# PIC32.net
KiCad netlist of a schematic drawn in EAGLE
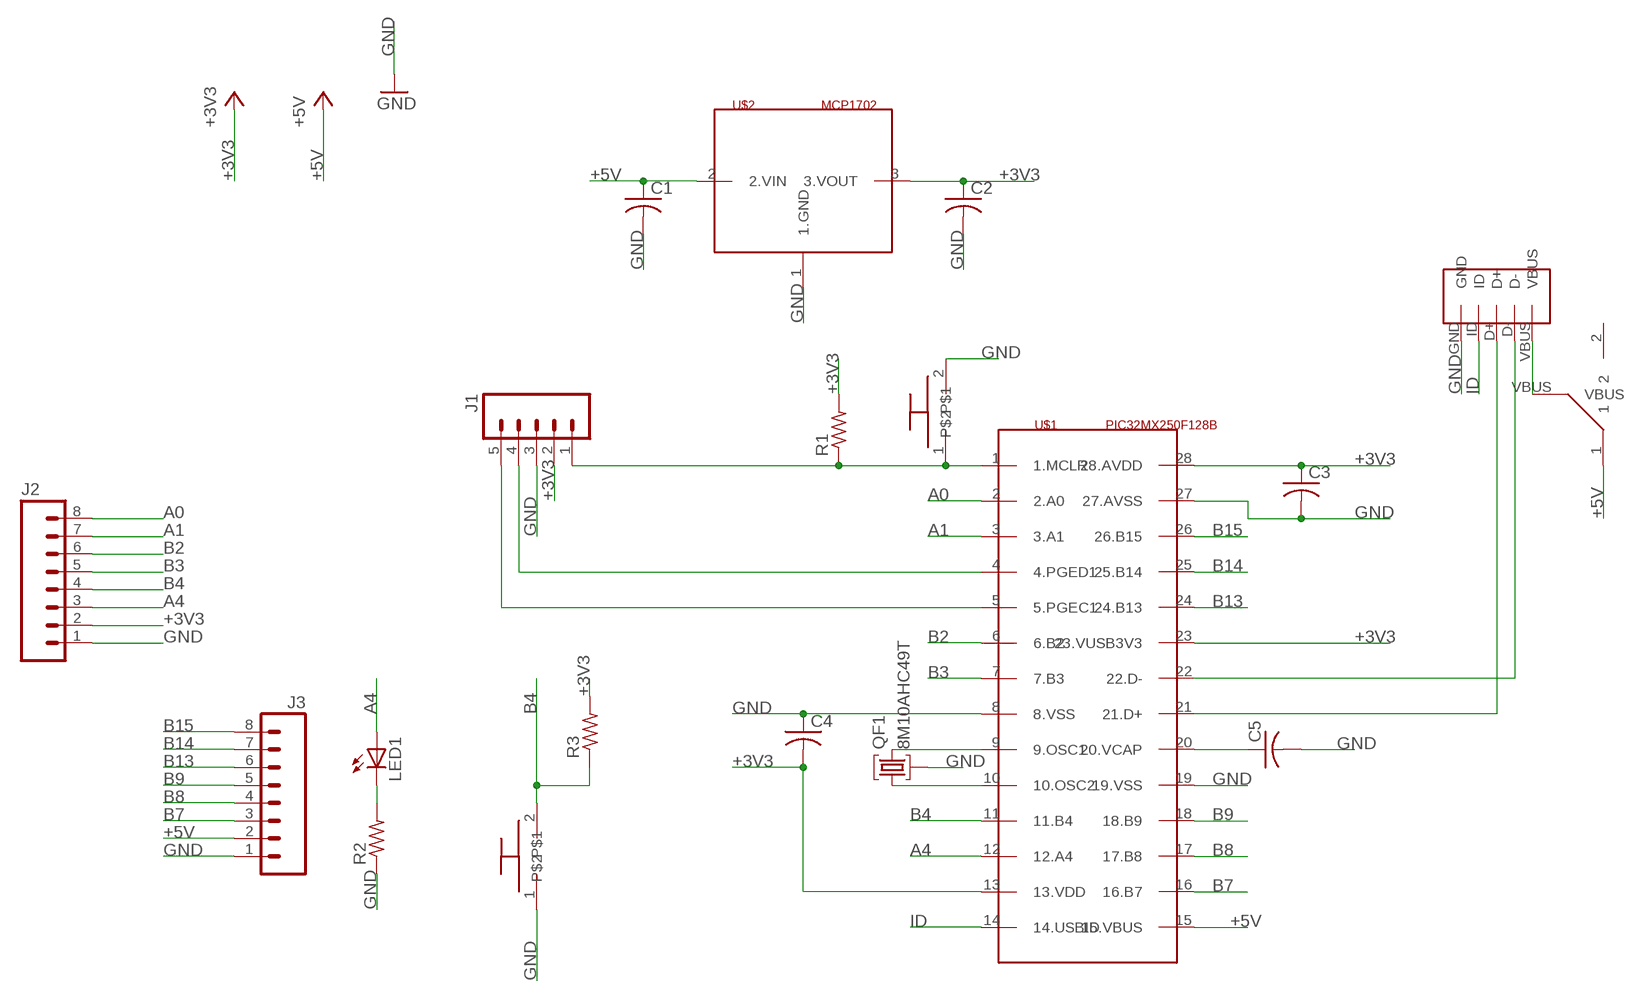
[diagram p0: schematic, sheet 1]

(export (version "E")
  (design (tool "Eeschema 10.0.6"))
  (components
    (comp (ref "C1")
      (value "C-US025-024X044")
      (footprint "eagle-import:C025-024X044")
      (libsource (lib "eagle-import") (part "C-US025-024X044"))
    )
    (comp (ref "C2")
      (value "C-US025-024X044")
      (footprint "eagle-import:C025-024X044")
      (libsource (lib "eagle-import") (part "C-US025-024X044"))
    )
    (comp (ref "C3")
      (value "C-US025-024X044")
      (footprint "eagle-import:C025-024X044")
      (libsource (lib "eagle-import") (part "C-US025-024X044"))
    )
    (comp (ref "C4")
      (value "C-US025-024X044")
      (footprint "eagle-import:C025-024X044")
      (libsource (lib "eagle-import") (part "C-US025-024X044"))
    )
    (comp (ref "C5")
      (value "C-US025-030X050")
      (footprint "eagle-import:C025-030X050")
      (libsource (lib "eagle-import") (part "C-US025-030X050"))
    )
    (comp (ref "J1")
      (value "M05PTH")
      (footprint "eagle-import:1X05")
      (libsource (lib "eagle-import") (part "M05PTH"))
    )
    (comp (ref "J2")
      (value "M08")
      (footprint "eagle-import:1X08_ROUND")
      (libsource (lib "eagle-import") (part "M08"))
    )
    (comp (ref "J3")
      (value "M08")
      (footprint "eagle-import:1X08_ROUND")
      (libsource (lib "eagle-import") (part "M08"))
    )
    (comp (ref "LED1")
      (value "LED3MM")
      (footprint "eagle-import:LED3MM")
      (libsource (lib "eagle-import") (part "LED3MM"))
    )
    (comp (ref "QF1")
      (value "8M10AHC49T")
      (footprint "eagle-import:HC49U")
      (libsource (lib "eagle-import") (part "8M10AHC49T"))
    )
    (comp (ref "R1")
      (value "R-US_0207/10")
      (footprint "eagle-import:0207_10")
      (libsource (lib "eagle-import") (part "R-US_0207/10"))
    )
    (comp (ref "R2")
      (value "R-US_0207/10")
      (footprint "eagle-import:0207_10")
      (libsource (lib "eagle-import") (part "R-US_0207/10"))
    )
    (comp (ref "R3")
      (value "R-US_0207/10")
      (footprint "eagle-import:0207_10")
      (libsource (lib "eagle-import") (part "R-US_0207/10"))
    )
    (comp (ref "U$1")
      (value "PIC32MX250F128B")
      (footprint "eagle-import:DIL28-3")
      (libsource (lib "eagle-import") (part "PIC32MX250F128B"))
    )
    (comp (ref "U$2")
      (value "MCP1702")
      (footprint "eagle-import:TO92-EBC")
      (libsource (lib "eagle-import") (part "MCP1702"))
    )
    (comp (ref "U$3")
      (value "PUSHBUTTON")
      (footprint "eagle-import:PUSHBUTTON")
      (libsource (lib "eagle-import") (part "PUSHBUTTON"))
    )
    (comp (ref "U$4")
      (value "USB")
      (footprint "eagle-import:USB-MB-H")
      (libsource (lib "eagle-import") (part "USB"))
    )
    (comp (ref "U$5")
      (value "PUSHBUTTON")
      (footprint "eagle-import:PUSHBUTTON")
      (libsource (lib "eagle-import") (part "PUSHBUTTON"))
    )
    (comp (ref "U$6")
      (value "SLIDESWITCH")
      (footprint "eagle-import:SLIDESWITCH")
      (libsource (lib "eagle-import") (part "SLIDESWITCH"))
    )
  )
  (nets
    (net (code "1") (name "+3V3") (class "Default")
      (node (ref "C2") (pin "1") (pinfunction "1_1") (pintype "passive"))
      (node (ref "C3") (pin "1") (pinfunction "1_1") (pintype "passive"))
      (node (ref "C4") (pin "2") (pinfunction "2_2") (pintype "passive"))
      (node (ref "J1") (pin "2") (pinfunction "2_2") (pintype "passive"))
      (node (ref "J2") (pin "2") (pinfunction "2_2") (pintype "passive"))
      (node (ref "R1") (pin "2") (pinfunction "2_2") (pintype "passive"))
      (node (ref "R3") (pin "2") (pinfunction "2_2") (pintype "passive"))
      (node (ref "U$1") (pin "13") (pinfunction "13.VDD_13") (pintype "bidirectional"))
      (node (ref "U$1") (pin "23") (pinfunction "23.VUSB3V3_23") (pintype "bidirectional"))
      (node (ref "U$1") (pin "28") (pinfunction "28.AVDD_28") (pintype "bidirectional"))
      (node (ref "U$2") (pin "3") (pinfunction "3.VOUT_3") (pintype "bidirectional"))
    )
    (net (code "2") (name "+5V") (class "Default")
      (node (ref "C1") (pin "1") (pinfunction "1_1") (pintype "passive"))
      (node (ref "J3") (pin "2") (pinfunction "2_2") (pintype "passive"))
      (node (ref "U$1") (pin "15") (pinfunction "15.VBUS_15") (pintype "bidirectional"))
      (node (ref "U$2") (pin "2") (pinfunction "2.VIN_2") (pintype "bidirectional"))
      (node (ref "U$6") (pin "1") (pinfunction "1_1") (pintype "bidirectional"))
    )
    (net (code "3") (name "/A0") (class "Default")
      (node (ref "J2") (pin "8") (pinfunction "8_8") (pintype "passive"))
      (node (ref "U$1") (pin "2") (pinfunction "2.A0_2") (pintype "bidirectional"))
    )
    (net (code "4") (name "/A1") (class "Default")
      (node (ref "J2") (pin "7") (pinfunction "7_7") (pintype "passive"))
      (node (ref "U$1") (pin "3") (pinfunction "3.A1_3") (pintype "bidirectional"))
    )
    (net (code "5") (name "/A4") (class "Default")
      (node (ref "J2") (pin "3") (pinfunction "3_3") (pintype "passive"))
      (node (ref "LED1") (pin "A") (pinfunction "A_A") (pintype "passive"))
      (node (ref "U$1") (pin "12") (pinfunction "12.A4_12") (pintype "bidirectional"))
    )
    (net (code "6") (name "/B2") (class "Default")
      (node (ref "J2") (pin "6") (pinfunction "6_6") (pintype "passive"))
      (node (ref "U$1") (pin "6") (pinfunction "6.B2_6") (pintype "bidirectional"))
    )
    (net (code "7") (name "/B3") (class "Default")
      (node (ref "J2") (pin "5") (pinfunction "5_5") (pintype "passive"))
      (node (ref "U$1") (pin "7") (pinfunction "7.B3_7") (pintype "bidirectional"))
    )
    (net (code "8") (name "/B4") (class "Default")
      (node (ref "J2") (pin "4") (pinfunction "4_4") (pintype "passive"))
      (node (ref "R3") (pin "1") (pinfunction "1_1") (pintype "passive"))
      (node (ref "U$1") (pin "11") (pinfunction "11.B4_11") (pintype "bidirectional"))
      (node (ref "U$5") (pin "2") (pinfunction "P$2_2") (pintype "bidirectional"))
    )
    (net (code "9") (name "/B7") (class "Default")
      (node (ref "J3") (pin "3") (pinfunction "3_3") (pintype "passive"))
      (node (ref "U$1") (pin "16") (pinfunction "16.B7_16") (pintype "bidirectional"))
    )
    (net (code "10") (name "/B8") (class "Default")
      (node (ref "J3") (pin "4") (pinfunction "4_4") (pintype "passive"))
      (node (ref "U$1") (pin "17") (pinfunction "17.B8_17") (pintype "bidirectional"))
    )
    (net (code "11") (name "/B9") (class "Default")
      (node (ref "J3") (pin "5") (pinfunction "5_5") (pintype "passive"))
      (node (ref "U$1") (pin "18") (pinfunction "18.B9_18") (pintype "bidirectional"))
    )
    (net (code "12") (name "/B13") (class "Default")
      (node (ref "J3") (pin "6") (pinfunction "6_6") (pintype "passive"))
      (node (ref "U$1") (pin "24") (pinfunction "24.B13_24") (pintype "bidirectional"))
    )
    (net (code "13") (name "/B14") (class "Default")
      (node (ref "J3") (pin "7") (pinfunction "7_7") (pintype "passive"))
      (node (ref "U$1") (pin "25") (pinfunction "25.B14_25") (pintype "bidirectional"))
    )
    (net (code "14") (name "/B15") (class "Default")
      (node (ref "J3") (pin "8") (pinfunction "8_8") (pintype "passive"))
      (node (ref "U$1") (pin "26") (pinfunction "26.B15_26") (pintype "bidirectional"))
    )
    (net (code "15") (name "/ID") (class "Default")
      (node (ref "U$1") (pin "14") (pinfunction "14.USBID_14") (pintype "bidirectional"))
      (node (ref "U$4") (pin "ID") (pinfunction "ID_ID") (pintype "bidirectional"))
    )
    (net (code "16") (name "GND") (class "Default")
      (node (ref "C1") (pin "2") (pinfunction "2_2") (pintype "passive"))
      (node (ref "C2") (pin "2") (pinfunction "2_2") (pintype "passive"))
      (node (ref "C3") (pin "2") (pinfunction "2_2") (pintype "passive"))
      (node (ref "C4") (pin "1") (pinfunction "1_1") (pintype "passive"))
      (node (ref "C5") (pin "2") (pinfunction "2_2") (pintype "passive"))
      (node (ref "J1") (pin "3") (pinfunction "3_3") (pintype "passive"))
      (node (ref "J2") (pin "1") (pinfunction "1_1") (pintype "passive"))
      (node (ref "J3") (pin "1") (pinfunction "1_1") (pintype "passive"))
      (node (ref "QF1") (pin "2") (pinfunction "2_2") (pintype "passive"))
      (node (ref "QF1") (pin "3") (pinfunction "3_3") (pintype "passive"))
      (node (ref "R2") (pin "1") (pinfunction "1_1") (pintype "passive"))
      (node (ref "U$1") (pin "19") (pinfunction "19.VSS_19") (pintype "bidirectional"))
      (node (ref "U$1") (pin "27") (pinfunction "27.AVSS_27") (pintype "bidirectional"))
      (node (ref "U$1") (pin "8") (pinfunction "8.VSS_8") (pintype "bidirectional"))
      (node (ref "U$1") (pin "9") (pinfunction "9.OSC1_9") (pintype "bidirectional"))
      (node (ref "U$2") (pin "1") (pinfunction "1.GND_1") (pintype "bidirectional"))
      (node (ref "U$3") (pin "2") (pinfunction "P$2_2") (pintype "bidirectional"))
      (node (ref "U$4") (pin "GND") (pinfunction "GND_GND") (pintype "bidirectional"))
      (node (ref "U$5") (pin "1") (pinfunction "P$1_1") (pintype "bidirectional"))
    )
    (net (code "17") (name "Net-(LED1-C)") (class "Default")
      (node (ref "LED1") (pin "K") (pinfunction "C_K") (pintype "passive"))
      (node (ref "R2") (pin "2") (pinfunction "2_2") (pintype "passive"))
    )
    (net (code "18") (name "Net-(U$1-1.MCLR)") (class "Default")
      (node (ref "J1") (pin "1") (pinfunction "1_1") (pintype "passive"))
      (node (ref "R1") (pin "1") (pinfunction "1_1") (pintype "passive"))
      (node (ref "U$1") (pin "1") (pinfunction "1.MCLR_1") (pintype "bidirectional"))
      (node (ref "U$3") (pin "1") (pinfunction "P$1_1") (pintype "bidirectional"))
    )
    (net (code "19") (name "Net-(U$1-4.PGED1)") (class "Default")
      (node (ref "J1") (pin "4") (pinfunction "4_4") (pintype "passive"))
      (node (ref "U$1") (pin "4") (pinfunction "4.PGED1_4") (pintype "bidirectional"))
    )
    (net (code "20") (name "Net-(U$1-5.PGEC1)") (class "Default")
      (node (ref "J1") (pin "5") (pinfunction "5_5") (pintype "passive"))
      (node (ref "U$1") (pin "5") (pinfunction "5.PGEC1_5") (pintype "bidirectional"))
    )
    (net (code "21") (name "Net-(U$1-10.OSC2)") (class "Default")
      (node (ref "QF1") (pin "1") (pinfunction "1_1") (pintype "passive"))
      (node (ref "U$1") (pin "10") (pinfunction "10.OSC2_10") (pintype "bidirectional"))
    )
    (net (code "22") (name "Net-(U$1-20.VCAP)") (class "Default")
      (node (ref "C5") (pin "1") (pinfunction "1_1") (pintype "passive"))
      (node (ref "U$1") (pin "20") (pinfunction "20.VCAP_20") (pintype "bidirectional"))
    )
    (net (code "23") (name "Net-(U$1-21.D+)") (class "Default")
      (node (ref "U$1") (pin "21") (pinfunction "21.D+_21") (pintype "bidirectional"))
      (node (ref "U$4") (pin "D+") (pinfunction "D+_D+") (pintype "bidirectional"))
    )
    (net (code "24") (name "Net-(U$1-22.D-)") (class "Default")
      (node (ref "U$1") (pin "22") (pinfunction "22.D-_22") (pintype "bidirectional"))
      (node (ref "U$4") (pin "D-") (pinfunction "D-_D-") (pintype "bidirectional"))
    )
    (net (code "25") (name "Net-(U$4-PadVBUS)") (class "Default")
      (node (ref "U$4") (pin "VBUS") (pinfunction "VBUS_VBUS") (pintype "bidirectional"))
      (node (ref "U$6") (pin "VBUS") (pinfunction "VBUS_VBUS") (pintype "bidirectional"))
    )
    (net (code "26") (name "unconnected-(U$6-Pad2)") (class "Default")
      (node (ref "U$6") (pin "2") (pinfunction "2_2") (pintype "bidirectional"))
    )
  )
)
